# cyberlamp.net
KiCad netlist of a schematic drawn in Altium Designer
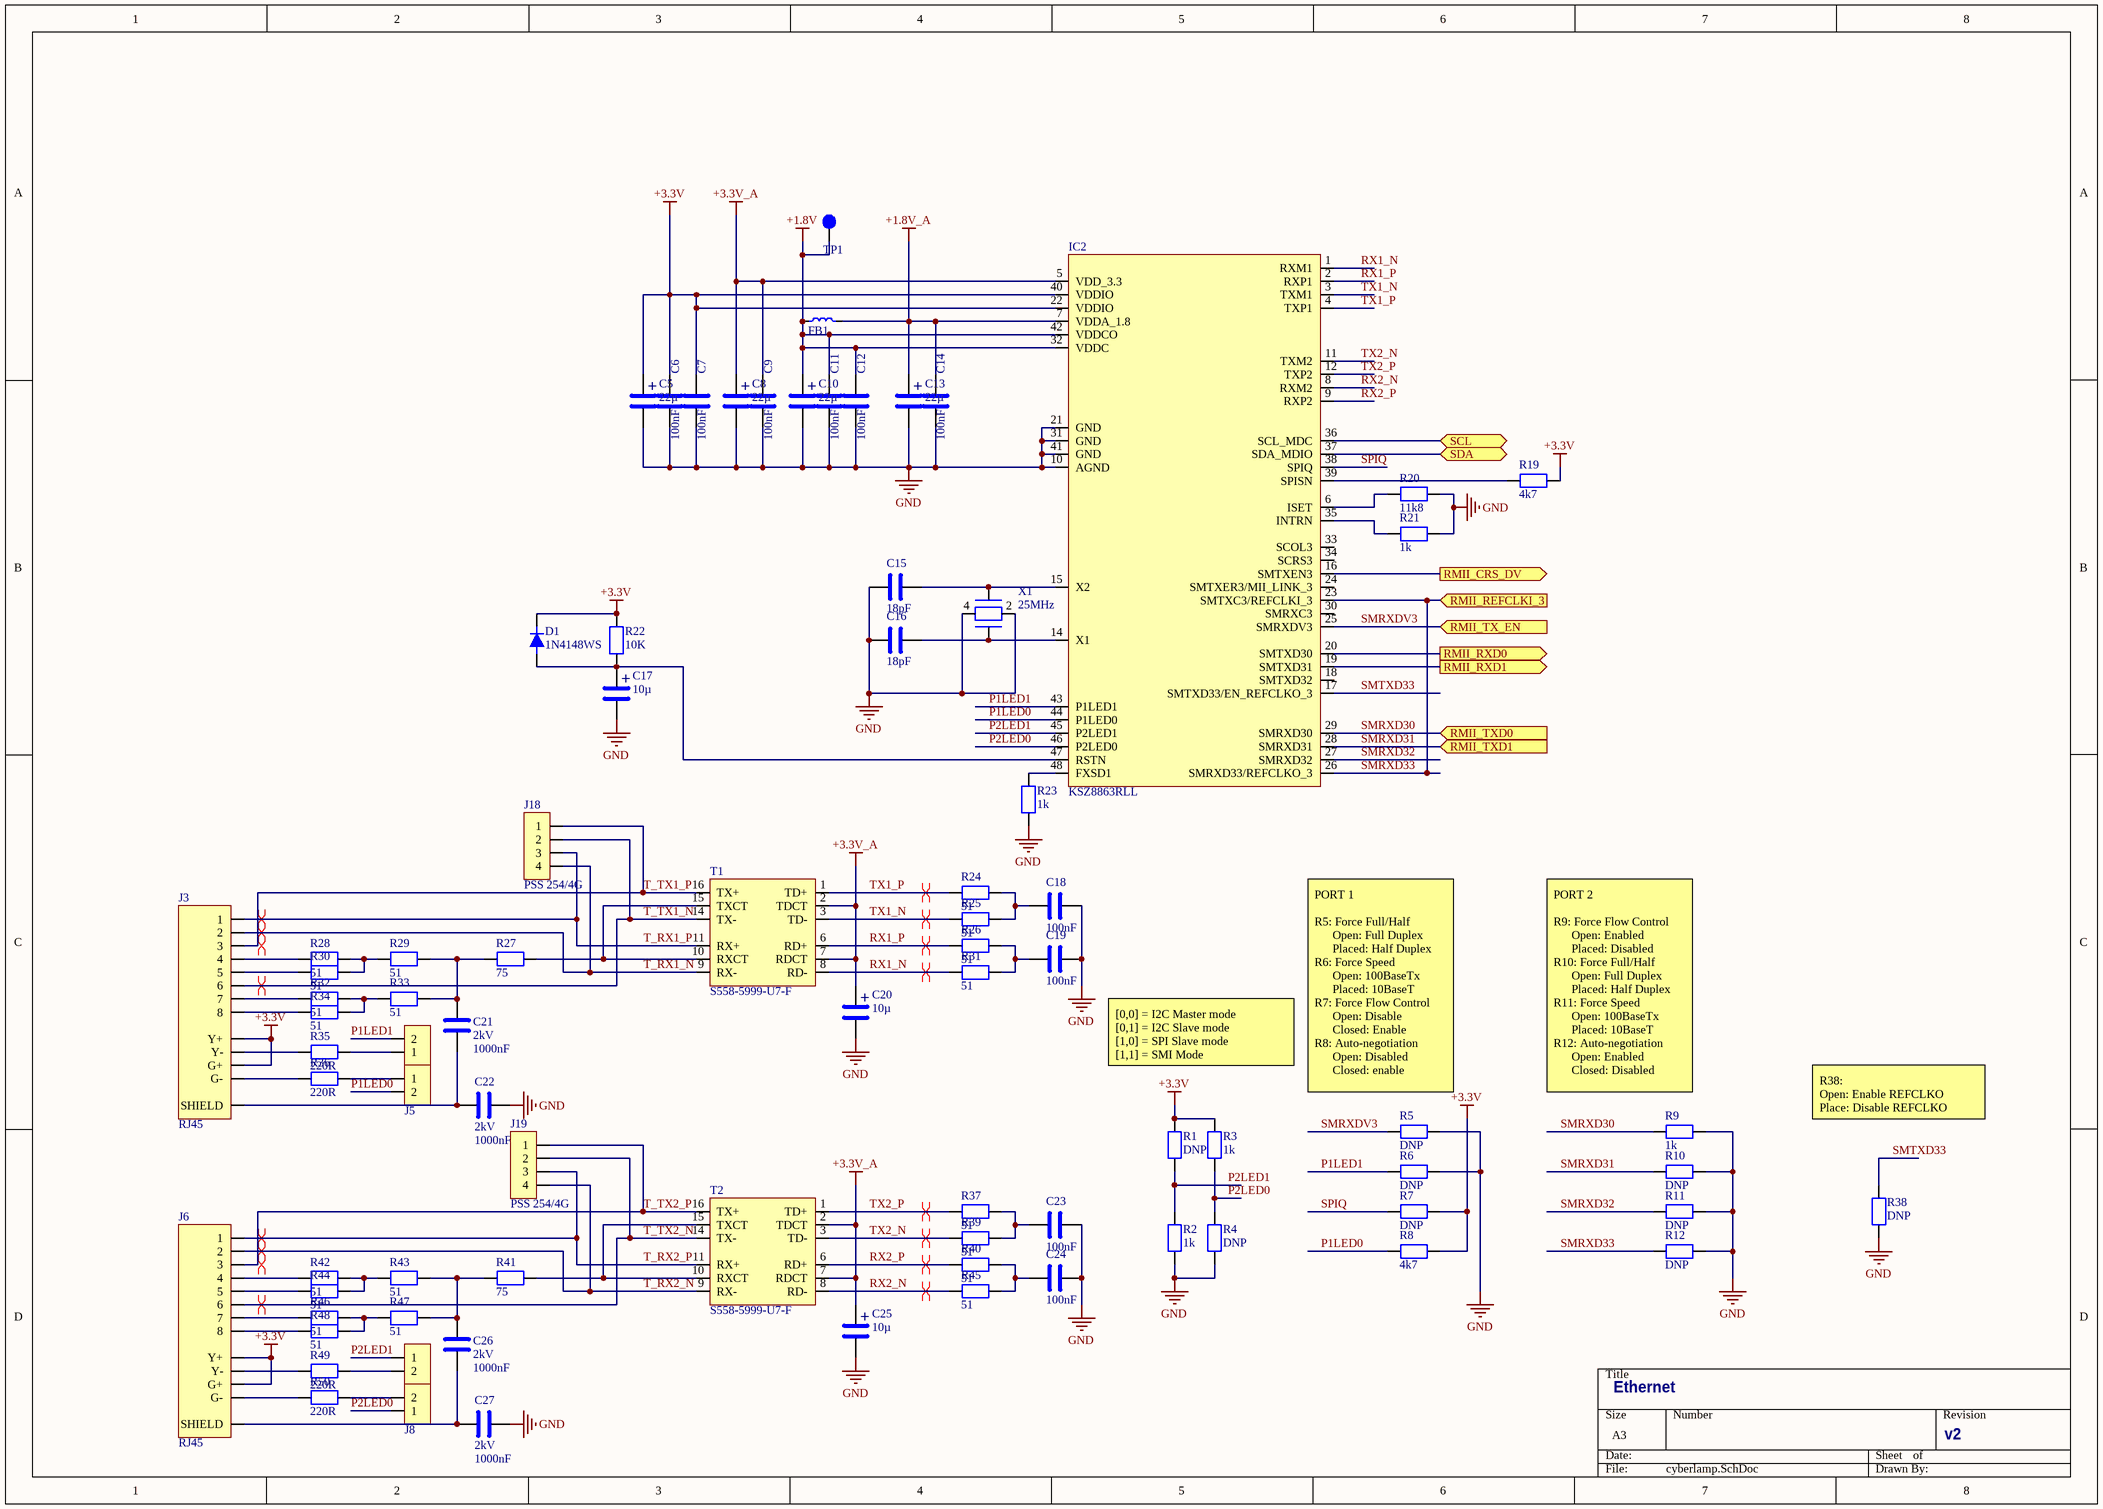
[diagram p0: cyberlamp.SchDoc]

(export (version "E")
  (design (tool "Eeschema 10.0.6"))
  (components
    (comp (ref "C5")
      (value "22µ")
      (footprint "WCAP-ASLU")
      (fields (field (name "VOLTAGE") "6.3V") (field (name "Comment") "Elko 22µF 6.3V WE"))
      (libsource (lib "elko") (part "Elko 22µF 6.3V WE"))
    )
    (comp (ref "C6")
      (value "100nF")
      (footprint "0603")
      (description "100nF 50V MLCC 0603")
      (fields (field (name "VOLTAGE") "50V"))
      (libsource (lib "capacitors") (part "100nF 50V MLCC 0603"))
    )
    (comp (ref "C7")
      (value "100nF")
      (footprint "0603")
      (description "100nF 50V MLCC 0603")
      (fields (field (name "VOLTAGE") "50V"))
      (libsource (lib "capacitors") (part "100nF 50V MLCC 0603"))
    )
    (comp (ref "C8")
      (value "22µ")
      (footprint "WCAP-ASLU")
      (fields (field (name "VOLTAGE") "6.3V") (field (name "Comment") "Elko 22µF 6.3V WE"))
      (libsource (lib "elko") (part "Elko 22µF 6.3V WE"))
    )
    (comp (ref "C9")
      (value "100nF")
      (footprint "0603")
      (description "100nF 50V MLCC 0603")
      (fields (field (name "VOLTAGE") "50V"))
      (libsource (lib "capacitors") (part "100nF 50V MLCC 0603"))
    )
    (comp (ref "C10")
      (value "22µ")
      (footprint "WCAP-ASLU")
      (fields (field (name "VOLTAGE") "6.3V") (field (name "Comment") "Elko 22µF 6.3V WE"))
      (libsource (lib "elko") (part "Elko 22µF 6.3V WE"))
    )
    (comp (ref "C11")
      (value "100nF")
      (footprint "0603")
      (description "100nF 50V MLCC 0603")
      (fields (field (name "VOLTAGE") "50V"))
      (libsource (lib "capacitors") (part "100nF 50V MLCC 0603"))
    )
    (comp (ref "C12")
      (value "100nF")
      (footprint "0603")
      (description "100nF 50V MLCC 0603")
      (fields (field (name "VOLTAGE") "50V"))
      (libsource (lib "capacitors") (part "100nF 50V MLCC 0603"))
    )
    (comp (ref "C13")
      (value "22µ")
      (footprint "WCAP-ASLU")
      (fields (field (name "VOLTAGE") "6.3V") (field (name "Comment") "Elko 22µF 6.3V WE"))
      (libsource (lib "elko") (part "Elko 22µF 6.3V WE"))
    )
    (comp (ref "C14")
      (value "100nF")
      (footprint "0603")
      (description "100nF 50V MLCC 0603")
      (fields (field (name "VOLTAGE") "50V"))
      (libsource (lib "capacitors") (part "100nF 50V MLCC 0603"))
    )
    (comp (ref "C15")
      (value "18pF")
      (footprint "0603")
      (description "18pF 50V MLCC 0603")
      (fields (field (name "VOLTAGE") "50V"))
      (libsource (lib "capacitors") (part "18pF 50V MLCC 0603"))
    )
    (comp (ref "C16")
      (value "18pF")
      (footprint "0603")
      (description "18pF 50V MLCC 0603")
      (fields (field (name "VOLTAGE") "50V"))
      (libsource (lib "capacitors") (part "18pF 50V MLCC 0603"))
    )
    (comp (ref "C17")
      (value "10µ")
      (footprint "Panasonic_b")
      (fields (field (name "VOLTAGE") "16V") (field (name "Comment") "Elko_10uF_16V_PanasonicB"))
      (libsource (lib "elkos") (part "Elko_10uF_16V_PanasonicB"))
    )
    (comp (ref "C18")
      (value "100nF")
      (footprint "0603")
      (description "100nF 50V MLCC 0603")
      (fields (field (name "VOLTAGE") "50V"))
      (libsource (lib "capacitors") (part "100nF 50V MLCC 0603"))
    )
    (comp (ref "C19")
      (value "100nF")
      (footprint "0603")
      (description "100nF 50V MLCC 0603")
      (fields (field (name "VOLTAGE") "50V"))
      (libsource (lib "capacitors") (part "100nF 50V MLCC 0603"))
    )
    (comp (ref "C20")
      (value "10µ")
      (footprint "Panasonic_b")
      (fields (field (name "VOLTAGE") "16V") (field (name "Comment") "Elko_10uF_16V_PanasonicB"))
      (libsource (lib "elkos") (part "Elko_10uF_16V_PanasonicB"))
    )
    (comp (ref "C21")
      (value "1000nF")
      (footprint "1206")
      (description "1000nF 2kV X7R 1206")
      (fields (field (name "VOLTAGE") "2kV") (field (name "Comment") "NP0"))
      (libsource (lib "capacitors") (part "1000nF 2kV X7R 1206"))
    )
    (comp (ref "C22")
      (value "1000nF")
      (footprint "1206")
      (description "1000nF 2kV X7R 1206")
      (fields (field (name "VOLTAGE") "2kV") (field (name "Comment") "NP0"))
      (libsource (lib "capacitors") (part "1000nF 2kV X7R 1206"))
    )
    (comp (ref "C23")
      (value "100nF")
      (footprint "0603")
      (description "100nF 50V MLCC 0603")
      (fields (field (name "VOLTAGE") "50V"))
      (libsource (lib "capacitors") (part "100nF 50V MLCC 0603"))
    )
    (comp (ref "C24")
      (value "100nF")
      (footprint "0603")
      (description "100nF 50V MLCC 0603")
      (fields (field (name "VOLTAGE") "50V"))
      (libsource (lib "capacitors") (part "100nF 50V MLCC 0603"))
    )
    (comp (ref "C25")
      (value "10µ")
      (footprint "Panasonic_b")
      (fields (field (name "VOLTAGE") "16V") (field (name "Comment") "Elko_10uF_16V_PanasonicB"))
      (libsource (lib "elkos") (part "Elko_10uF_16V_PanasonicB"))
    )
    (comp (ref "C26")
      (value "1000nF")
      (footprint "1206")
      (description "1000nF 2kV X7R 1206")
      (fields (field (name "VOLTAGE") "2kV") (field (name "Comment") "NP0"))
      (libsource (lib "capacitors") (part "1000nF 2kV X7R 1206"))
    )
    (comp (ref "C27")
      (value "1000nF")
      (footprint "1206")
      (description "1000nF 2kV X7R 1206")
      (fields (field (name "VOLTAGE") "2kV") (field (name "Comment") "NP0"))
      (libsource (lib "capacitors") (part "1000nF 2kV X7R 1206"))
    )
    (comp (ref "D1")
      (value "1N4148WS")
      (footprint "SOD323")
      (description "Small signal diode")
      (libsource (lib "diodes") (part "1N4148WS"))
    )
    (comp (ref "FB1")
      (value "HI1206N101R-10")
      (footprint "1206")
      (description "3A ferrit bead")
      (libsource (lib "inductors") (part "HI1206N101R-10"))
    )
    (comp (ref "IC2")
      (value "KSZ8863RLL")
      (footprint "LQFP48")
      (description "Dual port ethernet switch with RMII")
      (libsource (lib "misc") (part "KSZ8863RLL"))
    )
    (comp (ref "J3")
      (value "RJ45")
      (footprint "MTJ-88ARX1-FSM-PG-LH")
      (description "RJ45, shielded with LED")
      (libsource (lib "connectors_pc") (part "MTJ-88ARX1-FSM-PG-LH"))
    )
    (comp (ref "J4")
      (value "SL 1X2G 2,54")
      (footprint "SL_1x2 2.54mm")
      (description "Stiftleiste 2pol 2.54mm")
      (libsource (lib "connectors_sl") (part "SL 1X2G 2,54"))
    )
    (comp (ref "J5")
      (value "SL 1X2G 2,54")
      (footprint "SL_1x2 2.54mm")
      (description "Stiftleiste 2pol 2.54mm")
      (libsource (lib "") (part "SL 1X2G 2,54_1"))
    )
    (comp (ref "J6")
      (value "RJ45")
      (footprint "MTJ-88ARX1-FSM-PG-LH")
      (description "RJ45, shielded with LED")
      (libsource (lib "connectors_pc") (part "MTJ-88ARX1-FSM-PG-LH"))
    )
    (comp (ref "J7")
      (value "SL 1X2G 2,54")
      (footprint "SL_1x2 2.54mm")
      (description "Stiftleiste 2pol 2.54mm")
      (libsource (lib "") (part "SL 1X2G 2,54_1"))
    )
    (comp (ref "J8")
      (value "SL 1X2G 2,54")
      (footprint "SL_1x2 2.54mm")
      (description "Stiftleiste 2pol 2.54mm")
      (libsource (lib "connectors_sl") (part "SL 1X2G 2,54"))
    )
    (comp (ref "J18")
      (value "PSS 254/4G")
      (footprint "PSS 4pol")
      (description "PSS 4pol wire-to-board-connector")
      (libsource (lib "connectors_pss") (part "PSS 254/4G"))
    )
    (comp (ref "J19")
      (value "PSS 254/4G")
      (footprint "PSS 4pol")
      (description "PSS 4pol wire-to-board-connector")
      (libsource (lib "connectors_pss") (part "PSS 254/4G"))
    )
    (comp (ref "R1")
      (value "DNP")
      (footprint "res0603")
      (description "1k 100mW 0603")
      (fields (field (name "TOLERANCE") "1%"))
      (libsource (lib "resistors0603") (part "1k 100mW 0603"))
    )
    (comp (ref "R2")
      (value "1k")
      (footprint "res0603")
      (description "1k 100mW 0603")
      (fields (field (name "TOLERANCE") "1%"))
      (libsource (lib "resistors0603") (part "1k 100mW 0603"))
    )
    (comp (ref "R3")
      (value "1k")
      (footprint "res0603")
      (description "1k 100mW 0603")
      (fields (field (name "TOLERANCE") "1%"))
      (libsource (lib "resistors0603") (part "1k 100mW 0603"))
    )
    (comp (ref "R4")
      (value "DNP")
      (footprint "res0603")
      (description "1k 100mW 0603")
      (fields (field (name "TOLERANCE") "1%"))
      (libsource (lib "resistors0603") (part "1k 100mW 0603"))
    )
    (comp (ref "R5")
      (value "DNP")
      (footprint "res0603")
      (description "1k 100mW 0603")
      (fields (field (name "TOLERANCE") "1%"))
      (libsource (lib "resistors0603") (part "1k 100mW 0603"))
    )
    (comp (ref "R6")
      (value "DNP")
      (footprint "res0603")
      (description "1k 100mW 0603")
      (fields (field (name "TOLERANCE") "1%"))
      (libsource (lib "resistors0603") (part "1k 100mW 0603"))
    )
    (comp (ref "R7")
      (value "DNP")
      (footprint "res0603")
      (description "4k7 100mW 0603")
      (libsource (lib "resistors") (part "4k7 100mW 0603"))
    )
    (comp (ref "R8")
      (value "4k7")
      (footprint "res0603")
      (description "4k7 100mW 0603")
      (libsource (lib "resistors") (part "4k7 100mW 0603"))
    )
    (comp (ref "R9")
      (value "1k")
      (footprint "res0603")
      (description "1k 100mW 0603")
      (fields (field (name "TOLERANCE") "1%"))
      (libsource (lib "resistors0603") (part "1k 100mW 0603"))
    )
    (comp (ref "R10")
      (value "DNP")
      (footprint "res0603")
      (description "1k 100mW 0603")
      (fields (field (name "TOLERANCE") "1%"))
      (libsource (lib "resistors0603") (part "1k 100mW 0603"))
    )
    (comp (ref "R11")
      (value "DNP")
      (footprint "res0603")
      (description "1k 100mW 0603")
      (fields (field (name "TOLERANCE") "1%"))
      (libsource (lib "resistors0603") (part "1k 100mW 0603"))
    )
    (comp (ref "R12")
      (value "DNP")
      (footprint "res0603")
      (description "1k 100mW 0603")
      (fields (field (name "TOLERANCE") "1%"))
      (libsource (lib "resistors0603") (part "1k 100mW 0603"))
    )
    (comp (ref "R19")
      (value "4k7")
      (footprint "res0603")
      (description "4k7 100mW 0603")
      (libsource (lib "resistors") (part "4k7 100mW 0603"))
    )
    (comp (ref "R20")
      (value "11k8")
      (footprint "res0603")
      (description "11k8 100mW 0603")
      (fields (field (name "TOLERANCE") "1%"))
      (libsource (lib "resistors0603") (part "11k8 100mW 0603"))
    )
    (comp (ref "R21")
      (value "1k")
      (footprint "res0603")
      (description "1k 100mW 0603")
      (fields (field (name "TOLERANCE") "1%"))
      (libsource (lib "resistors0603") (part "1k 100mW 0603"))
    )
    (comp (ref "R22")
      (value "10K")
      (footprint "res0603")
      (description "10K 100mW 0603")
      (fields (field (name "TOLERANCE") "1%"))
      (libsource (lib "resistors") (part "10K 100mW 0603"))
    )
    (comp (ref "R23")
      (value "1k")
      (footprint "res0603")
      (description "1k 100mW 0603")
      (fields (field (name "TOLERANCE") "1%"))
      (libsource (lib "resistors0603") (part "1k 100mW 0603"))
    )
    (comp (ref "R24")
      (value "51")
      (footprint "res0603")
      (description "51 100mW 0603")
      (fields (field (name "TOLERANCE") "5%") (field (name "Comment") "51R 100mW 0603"))
      (libsource (lib "resistors0603") (part "51R 100mW 0603"))
    )
    (comp (ref "R25")
      (value "51")
      (footprint "res0603")
      (description "51 100mW 0603")
      (fields (field (name "TOLERANCE") "5%") (field (name "Comment") "51R 100mW 0603"))
      (libsource (lib "resistors0603") (part "51R 100mW 0603"))
    )
    (comp (ref "R26")
      (value "51")
      (footprint "res0603")
      (description "51 100mW 0603")
      (fields (field (name "TOLERANCE") "5%") (field (name "Comment") "51R 100mW 0603"))
      (libsource (lib "resistors0603") (part "51R 100mW 0603"))
    )
    (comp (ref "R27")
      (value "75")
      (footprint "res0603")
      (description "75 100mW 0603")
      (fields (field (name "TOLERANCE") "1%") (field (name "Comment") "75R 100mW 0603"))
      (libsource (lib "resistors0603") (part "75R 100mW 0603"))
    )
    (comp (ref "R28")
      (value "51")
      (footprint "res0603")
      (description "51 100mW 0603")
      (fields (field (name "TOLERANCE") "5%") (field (name "Comment") "51R 100mW 0603"))
      (libsource (lib "resistors0603") (part "51R 100mW 0603"))
    )
    (comp (ref "R29")
      (value "51")
      (footprint "res0603")
      (description "51 100mW 0603")
      (fields (field (name "TOLERANCE") "5%") (field (name "Comment") "51R 100mW 0603"))
      (libsource (lib "resistors0603") (part "51R 100mW 0603"))
    )
    (comp (ref "R30")
      (value "51")
      (footprint "res0603")
      (description "51 100mW 0603")
      (fields (field (name "TOLERANCE") "5%") (field (name "Comment") "51R 100mW 0603"))
      (libsource (lib "resistors0603") (part "51R 100mW 0603"))
    )
    (comp (ref "R31")
      (value "51")
      (footprint "res0603")
      (description "51 100mW 0603")
      (fields (field (name "TOLERANCE") "5%") (field (name "Comment") "51R 100mW 0603"))
      (libsource (lib "resistors0603") (part "51R 100mW 0603"))
    )
    (comp (ref "R32")
      (value "51")
      (footprint "res0603")
      (description "51 100mW 0603")
      (fields (field (name "TOLERANCE") "5%") (field (name "Comment") "51R 100mW 0603"))
      (libsource (lib "resistors0603") (part "51R 100mW 0603"))
    )
    (comp (ref "R33")
      (value "51")
      (footprint "res0603")
      (description "51 100mW 0603")
      (fields (field (name "TOLERANCE") "5%") (field (name "Comment") "51R 100mW 0603"))
      (libsource (lib "resistors0603") (part "51R 100mW 0603"))
    )
    (comp (ref "R34")
      (value "51")
      (footprint "res0603")
      (description "51 100mW 0603")
      (fields (field (name "TOLERANCE") "5%") (field (name "Comment") "51R 100mW 0603"))
      (libsource (lib "resistors0603") (part "51R 100mW 0603"))
    )
    (comp (ref "R35")
      (value "220R")
      (footprint "res0603")
      (description "220R 100mW 0603")
      (fields (field (name "TOLERANCE") "1%"))
      (libsource (lib "resistors0603") (part "220R 100mW 0603"))
    )
    (comp (ref "R36")
      (value "220R")
      (footprint "res0603")
      (description "220R 100mW 0603")
      (fields (field (name "TOLERANCE") "1%"))
      (libsource (lib "resistors0603") (part "220R 100mW 0603"))
    )
    (comp (ref "R37")
      (value "51")
      (footprint "res0603")
      (description "51 100mW 0603")
      (fields (field (name "TOLERANCE") "5%") (field (name "Comment") "51R 100mW 0603"))
      (libsource (lib "resistors0603") (part "51R 100mW 0603"))
    )
    (comp (ref "R38")
      (value "DNP")
      (footprint "res0603")
      (description "1k 100mW 0603")
      (fields (field (name "TOLERANCE") "1%"))
      (libsource (lib "resistors0603") (part "1k 100mW 0603"))
    )
    (comp (ref "R39")
      (value "51")
      (footprint "res0603")
      (description "51 100mW 0603")
      (fields (field (name "TOLERANCE") "5%") (field (name "Comment") "51R 100mW 0603"))
      (libsource (lib "resistors0603") (part "51R 100mW 0603"))
    )
    (comp (ref "R40")
      (value "51")
      (footprint "res0603")
      (description "51 100mW 0603")
      (fields (field (name "TOLERANCE") "5%") (field (name "Comment") "51R 100mW 0603"))
      (libsource (lib "resistors0603") (part "51R 100mW 0603"))
    )
    (comp (ref "R41")
      (value "75")
      (footprint "res0603")
      (description "75 100mW 0603")
      (fields (field (name "TOLERANCE") "1%") (field (name "Comment") "75R 100mW 0603"))
      (libsource (lib "resistors0603") (part "75R 100mW 0603"))
    )
    (comp (ref "R42")
      (value "51")
      (footprint "res0603")
      (description "51 100mW 0603")
      (fields (field (name "TOLERANCE") "5%") (field (name "Comment") "51R 100mW 0603"))
      (libsource (lib "resistors0603") (part "51R 100mW 0603"))
    )
    (comp (ref "R43")
      (value "51")
      (footprint "res0603")
      (description "51 100mW 0603")
      (fields (field (name "TOLERANCE") "5%") (field (name "Comment") "51R 100mW 0603"))
      (libsource (lib "resistors0603") (part "51R 100mW 0603"))
    )
    (comp (ref "R44")
      (value "51")
      (footprint "res0603")
      (description "51 100mW 0603")
      (fields (field (name "TOLERANCE") "5%") (field (name "Comment") "51R 100mW 0603"))
      (libsource (lib "resistors0603") (part "51R 100mW 0603"))
    )
    (comp (ref "R45")
      (value "51")
      (footprint "res0603")
      (description "51 100mW 0603")
      (fields (field (name "TOLERANCE") "5%") (field (name "Comment") "51R 100mW 0603"))
      (libsource (lib "resistors0603") (part "51R 100mW 0603"))
    )
    (comp (ref "R46")
      (value "51")
      (footprint "res0603")
      (description "51 100mW 0603")
      (fields (field (name "TOLERANCE") "5%") (field (name "Comment") "51R 100mW 0603"))
      (libsource (lib "resistors0603") (part "51R 100mW 0603"))
    )
    (comp (ref "R47")
      (value "51")
      (footprint "res0603")
      (description "51 100mW 0603")
      (fields (field (name "TOLERANCE") "5%") (field (name "Comment") "51R 100mW 0603"))
      (libsource (lib "resistors0603") (part "51R 100mW 0603"))
    )
    (comp (ref "R48")
      (value "51")
      (footprint "res0603")
      (description "51 100mW 0603")
      (fields (field (name "TOLERANCE") "5%") (field (name "Comment") "51R 100mW 0603"))
      (libsource (lib "resistors0603") (part "51R 100mW 0603"))
    )
    (comp (ref "R49")
      (value "220R")
      (footprint "res0603")
      (description "220R 100mW 0603")
      (fields (field (name "TOLERANCE") "1%"))
      (libsource (lib "resistors0603") (part "220R 100mW 0603"))
    )
    (comp (ref "R50")
      (value "220R")
      (footprint "res0603")
      (description "220R 100mW 0603")
      (fields (field (name "TOLERANCE") "1%"))
      (libsource (lib "resistors0603") (part "220R 100mW 0603"))
    )
    (comp (ref "T1")
      (value "S558-5999-U7-F")
      (footprint "S558-5999-U7-F")
      (description "Ethernet transformer")
      (libsource (lib "inductors2") (part "S558-5999-U7-F"))
    )
    (comp (ref "T2")
      (value "S558-5999-U7-F")
      (footprint "S558-5999-U7-F")
      (description "Ethernet transformer")
      (libsource (lib "inductors2") (part "S558-5999-U7-F"))
    )
    (comp (ref "TP1") (value "testpoint") (footprint "testpoint") (libsource (lib "misc") (part "testpoint")))
    (comp (ref "X1")
      (value "25MHz")
      (footprint "ABM8")
      (description "ABM8 25MHz crystal")
      (libsource (lib "crystals") (part "ABM8-25.000MHZ-B2-T"))
    )
  )
  (nets
    (net (code "1") (name "+1.8V") (class "Default")
      (node (ref "C10") (pin "+") (pinfunction "+_+") (pintype "passive"))
      (node (ref "C11") (pin "1") (pinfunction "1_1") (pintype "passive"))
      (node (ref "C12") (pin "1") (pinfunction "1_1") (pintype "passive"))
      (node (ref "FB1") (pin "1") (pinfunction "1_1") (pintype "passive"))
      (node (ref "IC2") (pin "32") (pinfunction "VDDC_32") (pintype "passive"))
      (node (ref "IC2") (pin "42") (pinfunction "VDDCO_42") (pintype "passive"))
      (node (ref "TP1") (pin "1") (pinfunction "1_1") (pintype "passive"))
    )
    (net (code "2") (name "+1.8V_A") (class "Default")
      (node (ref "C13") (pin "+") (pinfunction "+_+") (pintype "passive"))
      (node (ref "C14") (pin "1") (pinfunction "1_1") (pintype "passive"))
      (node (ref "FB1") (pin "2") (pinfunction "2_2") (pintype "passive"))
      (node (ref "IC2") (pin "7") (pinfunction "VDDA_1.8_7") (pintype "passive"))
    )
    (net (code "3") (name "+3.3V") (class "Default")
      (node (ref "C5") (pin "+") (pinfunction "+_+") (pintype "passive"))
      (node (ref "C6") (pin "1") (pinfunction "1_1") (pintype "passive"))
      (node (ref "C7") (pin "1") (pinfunction "1_1") (pintype "passive"))
      (node (ref "D1") (pin "1") (pinfunction "1_1") (pintype "passive"))
      (node (ref "IC2") (pin "22") (pinfunction "VDDIO_22") (pintype "passive"))
      (node (ref "IC2") (pin "40") (pinfunction "VDDIO_40") (pintype "passive"))
      (node (ref "J3") (pin "10") (pinfunction "Y+_10") (pintype "passive"))
      (node (ref "J3") (pin "12") (pinfunction "G+_12") (pintype "passive"))
      (node (ref "J6") (pin "10") (pinfunction "Y+_10") (pintype "passive"))
      (node (ref "J6") (pin "12") (pinfunction "G+_12") (pintype "passive"))
      (node (ref "R1") (pin "2") (pinfunction "2_2") (pintype "passive"))
      (node (ref "R19") (pin "1") (pinfunction "1_1") (pintype "passive"))
      (node (ref "R22") (pin "2") (pinfunction "2_2") (pintype "passive"))
      (node (ref "R3") (pin "2") (pinfunction "2_2") (pintype "passive"))
      (node (ref "R7") (pin "1") (pinfunction "1_1") (pintype "passive"))
      (node (ref "R8") (pin "1") (pinfunction "1_1") (pintype "passive"))
    )
    (net (code "4") (name "+3.3V_A") (class "Default")
      (node (ref "C20") (pin "+") (pinfunction "+_+") (pintype "passive"))
      (node (ref "C25") (pin "+") (pinfunction "+_+") (pintype "passive"))
      (node (ref "C8") (pin "+") (pinfunction "+_+") (pintype "passive"))
      (node (ref "C9") (pin "1") (pinfunction "1_1") (pintype "passive"))
      (node (ref "IC2") (pin "5") (pinfunction "VDD_3.3_5") (pintype "passive"))
      (node (ref "T1") (pin "2") (pinfunction "TDCT_2") (pintype "passive"))
      (node (ref "T1") (pin "7") (pinfunction "RDCT_7") (pintype "passive"))
      (node (ref "T2") (pin "2") (pinfunction "TDCT_2") (pintype "passive"))
      (node (ref "T2") (pin "7") (pinfunction "RDCT_7") (pintype "passive"))
    )
    (net (code "5") (name "/P1LED0") (class "Default")
      (node (ref "IC2") (pin "44") (pinfunction "P1LED0_44") (pintype "passive"))
      (node (ref "J5") (pin "2") (pinfunction "2_2") (pintype "passive"))
      (node (ref "R8") (pin "2") (pinfunction "2_2") (pintype "passive"))
    )
    (net (code "6") (name "/P1LED1") (class "Default")
      (node (ref "IC2") (pin "43") (pinfunction "P1LED1_43") (pintype "passive"))
      (node (ref "J4") (pin "2") (pinfunction "2_2") (pintype "passive"))
      (node (ref "R6") (pin "2") (pinfunction "2_2") (pintype "passive"))
    )
    (net (code "7") (name "/P2LED0") (class "Default")
      (node (ref "IC2") (pin "46") (pinfunction "P2LED0_46") (pintype "passive"))
      (node (ref "J8") (pin "1") (pinfunction "1_1") (pintype "passive"))
      (node (ref "R3") (pin "1") (pinfunction "1_1") (pintype "passive"))
      (node (ref "R4") (pin "2") (pinfunction "2_2") (pintype "passive"))
    )
    (net (code "8") (name "/P2LED1") (class "Default")
      (node (ref "IC2") (pin "45") (pinfunction "P2LED1_45") (pintype "passive"))
      (node (ref "J7") (pin "1") (pinfunction "1_1") (pintype "passive"))
      (node (ref "R1") (pin "1") (pinfunction "1_1") (pintype "passive"))
      (node (ref "R2") (pin "2") (pinfunction "2_2") (pintype "passive"))
    )
    (net (code "9") (name "/RMII_CRS_DV") (class "Default")
      (node (ref "IC2") (pin "16") (pinfunction "SMTXEN3_16") (pintype "passive"))
    )
    (net (code "10") (name "/RMII_RXD0") (class "Default")
      (node (ref "IC2") (pin "20") (pinfunction "SMTXD30_20") (pintype "passive"))
    )
    (net (code "11") (name "/RMII_RXD1") (class "Default")
      (node (ref "IC2") (pin "19") (pinfunction "SMTXD31_19") (pintype "passive"))
    )
    (net (code "12") (name "/RX1_N") (class "Default")
      (node (ref "IC2") (pin "1") (pinfunction "RXM1_1") (pintype "passive"))
      (node (ref "R31") (pin "2") (pinfunction "2_2") (pintype "passive"))
      (node (ref "T1") (pin "8") (pinfunction "RD-_8") (pintype "passive"))
    )
    (net (code "13") (name "/RX1_P") (class "Default")
      (node (ref "IC2") (pin "2") (pinfunction "RXP1_2") (pintype "passive"))
      (node (ref "R26") (pin "2") (pinfunction "2_2") (pintype "passive"))
      (node (ref "T1") (pin "6") (pinfunction "RD+_6") (pintype "passive"))
    )
    (net (code "14") (name "/RX2_N") (class "Default")
      (node (ref "IC2") (pin "8") (pinfunction "RXM2_8") (pintype "passive"))
      (node (ref "R45") (pin "2") (pinfunction "2_2") (pintype "passive"))
      (node (ref "T2") (pin "8") (pinfunction "RD-_8") (pintype "passive"))
    )
    (net (code "15") (name "/RX2_P") (class "Default")
      (node (ref "IC2") (pin "9") (pinfunction "RXP2_9") (pintype "passive"))
      (node (ref "R40") (pin "2") (pinfunction "2_2") (pintype "passive"))
      (node (ref "T2") (pin "6") (pinfunction "RD+_6") (pintype "passive"))
    )
    (net (code "16") (name "/SCL") (class "Default")
      (node (ref "IC2") (pin "36") (pinfunction "SCL_MDC_36") (pintype "passive"))
    )
    (net (code "17") (name "/SDA") (class "Default")
      (node (ref "IC2") (pin "37") (pinfunction "SDA_MDIO_37") (pintype "passive"))
    )
    (net (code "18") (name "/SMRXD30") (class "Default")
      (node (ref "IC2") (pin "29") (pinfunction "SMRXD30_29") (pintype "passive"))
      (node (ref "R9") (pin "2") (pinfunction "2_2") (pintype "passive"))
    )
    (net (code "19") (name "/SMRXD31") (class "Default")
      (node (ref "IC2") (pin "28") (pinfunction "SMRXD31_28") (pintype "passive"))
      (node (ref "R10") (pin "2") (pinfunction "2_2") (pintype "passive"))
    )
    (net (code "20") (name "/SMRXD32") (class "Default")
      (node (ref "IC2") (pin "27") (pinfunction "SMRXD32_27") (pintype "passive"))
      (node (ref "R11") (pin "2") (pinfunction "2_2") (pintype "passive"))
    )
    (net (code "21") (name "/SMRXD33") (class "Default")
      (node (ref "IC2") (pin "23") (pinfunction "SMTXC3/REFCLKI_3_23") (pintype "passive"))
      (node (ref "IC2") (pin "26") (pinfunction "SMRXD33/REFCLKO_3_26") (pintype "passive"))
      (node (ref "R12") (pin "2") (pinfunction "2_2") (pintype "passive"))
    )
    (net (code "22") (name "/SMRXDV3") (class "Default")
      (node (ref "IC2") (pin "25") (pinfunction "SMRXDV3_25") (pintype "passive"))
      (node (ref "R5") (pin "2") (pinfunction "2_2") (pintype "passive"))
    )
    (net (code "23") (name "/SMTXD33") (class "Default")
      (node (ref "IC2") (pin "17") (pinfunction "SMTXD33/EN_REFCLKO_3_17") (pintype "passive"))
      (node (ref "R38") (pin "1") (pinfunction "1_1") (pintype "passive"))
    )
    (net (code "24") (name "/SPIQ") (class "Default")
      (node (ref "IC2") (pin "38") (pinfunction "SPIQ_38") (pintype "passive"))
      (node (ref "R7") (pin "2") (pinfunction "2_2") (pintype "passive"))
    )
    (net (code "25") (name "/TX1_N") (class "Default")
      (node (ref "IC2") (pin "3") (pinfunction "TXM1_3") (pintype "passive"))
      (node (ref "R25") (pin "2") (pinfunction "2_2") (pintype "passive"))
      (node (ref "T1") (pin "3") (pinfunction "TD-_3") (pintype "passive"))
    )
    (net (code "26") (name "/TX1_P") (class "Default")
      (node (ref "IC2") (pin "4") (pinfunction "TXP1_4") (pintype "passive"))
      (node (ref "R24") (pin "2") (pinfunction "2_2") (pintype "passive"))
      (node (ref "T1") (pin "1") (pinfunction "TD+_1") (pintype "passive"))
    )
    (net (code "27") (name "/TX2_N") (class "Default")
      (node (ref "IC2") (pin "11") (pinfunction "TXM2_11") (pintype "passive"))
      (node (ref "R39") (pin "2") (pinfunction "2_2") (pintype "passive"))
      (node (ref "T2") (pin "3") (pinfunction "TD-_3") (pintype "passive"))
    )
    (net (code "28") (name "/TX2_P") (class "Default")
      (node (ref "IC2") (pin "12") (pinfunction "TXP2_12") (pintype "passive"))
      (node (ref "R37") (pin "2") (pinfunction "2_2") (pintype "passive"))
      (node (ref "T2") (pin "1") (pinfunction "TD+_1") (pintype "passive"))
    )
    (net (code "29") (name "/T_RX1_N") (class "Default")
      (node (ref "J18") (pin "4") (pinfunction "4_4") (pintype "passive"))
      (node (ref "J3") (pin "2") (pinfunction "2_2") (pintype "passive"))
      (node (ref "T1") (pin "9") (pinfunction "RX-_9") (pintype "passive"))
    )
    (net (code "30") (name "/T_RX1_P") (class "Default")
      (node (ref "J18") (pin "3") (pinfunction "3_3") (pintype "passive"))
      (node (ref "J3") (pin "1") (pinfunction "1_1") (pintype "passive"))
      (node (ref "T1") (pin "11") (pinfunction "RX+_11") (pintype "passive"))
    )
    (net (code "31") (name "/T_RX2_N") (class "Default")
      (node (ref "J19") (pin "4") (pinfunction "4_4") (pintype "passive"))
      (node (ref "J6") (pin "2") (pinfunction "2_2") (pintype "passive"))
      (node (ref "T2") (pin "9") (pinfunction "RX-_9") (pintype "passive"))
    )
    (net (code "32") (name "/T_RX2_P") (class "Default")
      (node (ref "J19") (pin "3") (pinfunction "3_3") (pintype "passive"))
      (node (ref "J6") (pin "1") (pinfunction "1_1") (pintype "passive"))
      (node (ref "T2") (pin "11") (pinfunction "RX+_11") (pintype "passive"))
    )
    (net (code "33") (name "/T_TX1_N") (class "Default")
      (node (ref "J18") (pin "2") (pinfunction "2_2") (pintype "passive"))
      (node (ref "J3") (pin "6") (pinfunction "6_6") (pintype "passive"))
      (node (ref "T1") (pin "14") (pinfunction "TX-_14") (pintype "passive"))
    )
    (net (code "34") (name "/T_TX1_P") (class "Default")
      (node (ref "J18") (pin "1") (pinfunction "1_1") (pintype "passive"))
      (node (ref "J3") (pin "3") (pinfunction "3_3") (pintype "passive"))
      (node (ref "T1") (pin "16") (pinfunction "TX+_16") (pintype "passive"))
    )
    (net (code "35") (name "/T_TX2_N") (class "Default")
      (node (ref "J19") (pin "2") (pinfunction "2_2") (pintype "passive"))
      (node (ref "J6") (pin "6") (pinfunction "6_6") (pintype "passive"))
      (node (ref "T2") (pin "14") (pinfunction "TX-_14") (pintype "passive"))
    )
    (net (code "36") (name "/T_TX2_P") (class "Default")
      (node (ref "J19") (pin "1") (pinfunction "1_1") (pintype "passive"))
      (node (ref "J6") (pin "3") (pinfunction "3_3") (pintype "passive"))
      (node (ref "T2") (pin "16") (pinfunction "TX+_16") (pintype "passive"))
    )
    (net (code "37") (name "GND") (class "Default")
      (node (ref "C10") (pin "-") (pinfunction "-_-") (pintype "passive"))
      (node (ref "C11") (pin "2") (pinfunction "2_2") (pintype "passive"))
      (node (ref "C12") (pin "2") (pinfunction "2_2") (pintype "passive"))
      (node (ref "C13") (pin "-") (pinfunction "-_-") (pintype "passive"))
      (node (ref "C14") (pin "2") (pinfunction "2_2") (pintype "passive"))
      (node (ref "C15") (pin "1") (pinfunction "1_1") (pintype "passive"))
      (node (ref "C16") (pin "1") (pinfunction "1_1") (pintype "passive"))
      (node (ref "C17") (pin "-") (pinfunction "-_-") (pintype "passive"))
      (node (ref "C18") (pin "2") (pinfunction "2_2") (pintype "passive"))
      (node (ref "C19") (pin "2") (pinfunction "2_2") (pintype "passive"))
      (node (ref "C20") (pin "-") (pinfunction "-_-") (pintype "passive"))
      (node (ref "C22") (pin "1") (pinfunction "1_1") (pintype "passive"))
      (node (ref "C23") (pin "2") (pinfunction "2_2") (pintype "passive"))
      (node (ref "C24") (pin "2") (pinfunction "2_2") (pintype "passive"))
      (node (ref "C25") (pin "-") (pinfunction "-_-") (pintype "passive"))
      (node (ref "C27") (pin "1") (pinfunction "1_1") (pintype "passive"))
      (node (ref "C5") (pin "-") (pinfunction "-_-") (pintype "passive"))
      (node (ref "C6") (pin "2") (pinfunction "2_2") (pintype "passive"))
      (node (ref "C7") (pin "2") (pinfunction "2_2") (pintype "passive"))
      (node (ref "C8") (pin "-") (pinfunction "-_-") (pintype "passive"))
      (node (ref "C9") (pin "2") (pinfunction "2_2") (pintype "passive"))
      (node (ref "IC2") (pin "10") (pinfunction "AGND_10") (pintype "passive"))
      (node (ref "IC2") (pin "21") (pinfunction "GND_21") (pintype "passive"))
      (node (ref "IC2") (pin "31") (pinfunction "GND_31") (pintype "passive"))
      (node (ref "IC2") (pin "41") (pinfunction "GND_41") (pintype "passive"))
      (node (ref "R10") (pin "1") (pinfunction "1_1") (pintype "passive"))
      (node (ref "R11") (pin "1") (pinfunction "1_1") (pintype "passive"))
      (node (ref "R12") (pin "1") (pinfunction "1_1") (pintype "passive"))
      (node (ref "R2") (pin "1") (pinfunction "1_1") (pintype "passive"))
      (node (ref "R20") (pin "1") (pinfunction "1_1") (pintype "passive"))
      (node (ref "R21") (pin "1") (pinfunction "1_1") (pintype "passive"))
      (node (ref "R23") (pin "2") (pinfunction "2_2") (pintype "passive"))
      (node (ref "R38") (pin "2") (pinfunction "2_2") (pintype "passive"))
      (node (ref "R4") (pin "1") (pinfunction "1_1") (pintype "passive"))
      (node (ref "R5") (pin "1") (pinfunction "1_1") (pintype "passive"))
      (node (ref "R6") (pin "1") (pinfunction "1_1") (pintype "passive"))
      (node (ref "R9") (pin "1") (pinfunction "1_1") (pintype "passive"))
      (node (ref "X1") (pin "2") (pinfunction "2_2") (pintype "passive"))
      (node (ref "X1") (pin "4") (pinfunction "4_4") (pintype "passive"))
    )
    (net (code "38") (name "Net-(C18-Pad1)") (class "Default")
      (node (ref "C18") (pin "1") (pinfunction "1_1") (pintype "passive"))
      (node (ref "R24") (pin "1") (pinfunction "1_1") (pintype "passive"))
      (node (ref "R25") (pin "1") (pinfunction "1_1") (pintype "passive"))
    )
    (net (code "39") (name "Net-(C19-Pad1)") (class "Default")
      (node (ref "C19") (pin "1") (pinfunction "1_1") (pintype "passive"))
      (node (ref "R26") (pin "1") (pinfunction "1_1") (pintype "passive"))
      (node (ref "R31") (pin "1") (pinfunction "1_1") (pintype "passive"))
    )
    (net (code "40") (name "Net-(C21-Pad2)") (class "Default")
      (node (ref "C21") (pin "2") (pinfunction "2_2") (pintype "passive"))
      (node (ref "R27") (pin "2") (pinfunction "2_2") (pintype "passive"))
      (node (ref "R29") (pin "1") (pinfunction "1_1") (pintype "passive"))
      (node (ref "R33") (pin "1") (pinfunction "1_1") (pintype "passive"))
    )
    (net (code "41") (name "Net-(C23-Pad1)") (class "Default")
      (node (ref "C23") (pin "1") (pinfunction "1_1") (pintype "passive"))
      (node (ref "R37") (pin "1") (pinfunction "1_1") (pintype "passive"))
      (node (ref "R39") (pin "1") (pinfunction "1_1") (pintype "passive"))
    )
    (net (code "42") (name "Net-(C24-Pad1)") (class "Default")
      (node (ref "C24") (pin "1") (pinfunction "1_1") (pintype "passive"))
      (node (ref "R40") (pin "1") (pinfunction "1_1") (pintype "passive"))
      (node (ref "R45") (pin "1") (pinfunction "1_1") (pintype "passive"))
    )
    (net (code "43") (name "Net-(C26-Pad2)") (class "Default")
      (node (ref "C26") (pin "2") (pinfunction "2_2") (pintype "passive"))
      (node (ref "R41") (pin "2") (pinfunction "2_2") (pintype "passive"))
      (node (ref "R43") (pin "1") (pinfunction "1_1") (pintype "passive"))
      (node (ref "R47") (pin "1") (pinfunction "1_1") (pintype "passive"))
    )
    (net (code "44") (name "Net-(IC2-FXSD1)") (class "Default")
      (node (ref "IC2") (pin "48") (pinfunction "FXSD1_48") (pintype "passive"))
      (node (ref "R23") (pin "1") (pinfunction "1_1") (pintype "passive"))
    )
    (net (code "45") (name "Net-(IC2-INTRN)") (class "Default")
      (node (ref "IC2") (pin "35") (pinfunction "INTRN_35") (pintype "passive"))
      (node (ref "R21") (pin "2") (pinfunction "2_2") (pintype "passive"))
    )
    (net (code "46") (name "Net-(IC2-ISET)") (class "Default")
      (node (ref "IC2") (pin "6") (pinfunction "ISET_6") (pintype "passive"))
      (node (ref "R20") (pin "2") (pinfunction "2_2") (pintype "passive"))
    )
    (net (code "47") (name "Net-(IC2-RSTN)") (class "Default")
      (node (ref "C17") (pin "+") (pinfunction "+_+") (pintype "passive"))
      (node (ref "D1") (pin "2") (pinfunction "2_2") (pintype "passive"))
      (node (ref "IC2") (pin "47") (pinfunction "RSTN_47") (pintype "passive"))
      (node (ref "R22") (pin "1") (pinfunction "1_1") (pintype "passive"))
    )
    (net (code "48") (name "Net-(IC2-SPISN)") (class "Default")
      (node (ref "IC2") (pin "39") (pinfunction "SPISN_39") (pintype "passive"))
      (node (ref "R19") (pin "2") (pinfunction "2_2") (pintype "passive"))
    )
    (net (code "49") (name "Net-(IC2-X1)") (class "Default")
      (node (ref "C16") (pin "2") (pinfunction "2_2") (pintype "passive"))
      (node (ref "IC2") (pin "14") (pinfunction "X1_14") (pintype "passive"))
      (node (ref "X1") (pin "3") (pinfunction "3_3") (pintype "passive"))
    )
    (net (code "50") (name "Net-(IC2-X2)") (class "Default")
      (node (ref "C15") (pin "2") (pinfunction "2_2") (pintype "passive"))
      (node (ref "IC2") (pin "15") (pinfunction "X2_15") (pintype "passive"))
      (node (ref "X1") (pin "1") (pinfunction "1_1") (pintype "passive"))
    )
    (net (code "51") (name "Net-(J3-G-)") (class "Default")
      (node (ref "J3") (pin "11") (pinfunction "G-_11") (pintype "passive"))
      (node (ref "R36") (pin "2") (pinfunction "2_2") (pintype "passive"))
    )
    (net (code "52") (name "Net-(J3-Pad4)") (class "Default")
      (node (ref "J3") (pin "4") (pinfunction "4_4") (pintype "passive"))
      (node (ref "R28") (pin "2") (pinfunction "2_2") (pintype "passive"))
    )
    (net (code "53") (name "Net-(J3-Pad5)") (class "Default")
      (node (ref "J3") (pin "5") (pinfunction "5_5") (pintype "passive"))
      (node (ref "R30") (pin "2") (pinfunction "2_2") (pintype "passive"))
    )
    (net (code "54") (name "Net-(J3-Pad7)") (class "Default")
      (node (ref "J3") (pin "7") (pinfunction "7_7") (pintype "passive"))
      (node (ref "R32") (pin "2") (pinfunction "2_2") (pintype "passive"))
    )
    (net (code "55") (name "Net-(J3-Pad8)") (class "Default")
      (node (ref "J3") (pin "8") (pinfunction "8_8") (pintype "passive"))
      (node (ref "R34") (pin "2") (pinfunction "2_2") (pintype "passive"))
    )
    (net (code "56") (name "Net-(J3-SHIELD)") (class "Default")
      (node (ref "C21") (pin "1") (pinfunction "1_1") (pintype "passive"))
      (node (ref "C22") (pin "2") (pinfunction "2_2") (pintype "passive"))
      (node (ref "J3") (pin "13") (pinfunction "SHIELD_13") (pintype "passive"))
    )
    (net (code "57") (name "Net-(J3-Y-)") (class "Default")
      (node (ref "J3") (pin "9") (pinfunction "Y-_9") (pintype "passive"))
      (node (ref "R35") (pin "2") (pinfunction "2_2") (pintype "passive"))
    )
    (net (code "58") (name "Net-(J4-Pad1)") (class "Default")
      (node (ref "J4") (pin "1") (pinfunction "1_1") (pintype "passive"))
      (node (ref "R35") (pin "1") (pinfunction "1_1") (pintype "passive"))
    )
    (net (code "59") (name "Net-(J5-Pad1)") (class "Default")
      (node (ref "J5") (pin "1") (pinfunction "1_1") (pintype "passive"))
      (node (ref "R36") (pin "1") (pinfunction "1_1") (pintype "passive"))
    )
    (net (code "60") (name "Net-(J6-G-)") (class "Default")
      (node (ref "J6") (pin "11") (pinfunction "G-_11") (pintype "passive"))
      (node (ref "R50") (pin "2") (pinfunction "2_2") (pintype "passive"))
    )
    (net (code "61") (name "Net-(J6-Pad4)") (class "Default")
      (node (ref "J6") (pin "4") (pinfunction "4_4") (pintype "passive"))
      (node (ref "R42") (pin "2") (pinfunction "2_2") (pintype "passive"))
    )
    (net (code "62") (name "Net-(J6-Pad5)") (class "Default")
      (node (ref "J6") (pin "5") (pinfunction "5_5") (pintype "passive"))
      (node (ref "R44") (pin "2") (pinfunction "2_2") (pintype "passive"))
    )
    (net (code "63") (name "Net-(J6-Pad7)") (class "Default")
      (node (ref "J6") (pin "7") (pinfunction "7_7") (pintype "passive"))
      (node (ref "R46") (pin "2") (pinfunction "2_2") (pintype "passive"))
    )
    (net (code "64") (name "Net-(J6-Pad8)") (class "Default")
      (node (ref "J6") (pin "8") (pinfunction "8_8") (pintype "passive"))
      (node (ref "R48") (pin "2") (pinfunction "2_2") (pintype "passive"))
    )
    (net (code "65") (name "Net-(J6-SHIELD)") (class "Default")
      (node (ref "C26") (pin "1") (pinfunction "1_1") (pintype "passive"))
      (node (ref "C27") (pin "2") (pinfunction "2_2") (pintype "passive"))
      (node (ref "J6") (pin "13") (pinfunction "SHIELD_13") (pintype "passive"))
    )
    (net (code "66") (name "Net-(J6-Y-)") (class "Default")
      (node (ref "J6") (pin "9") (pinfunction "Y-_9") (pintype "passive"))
      (node (ref "R49") (pin "2") (pinfunction "2_2") (pintype "passive"))
    )
    (net (code "67") (name "Net-(J7-Pad2)") (class "Default")
      (node (ref "J7") (pin "2") (pinfunction "2_2") (pintype "passive"))
      (node (ref "R49") (pin "1") (pinfunction "1_1") (pintype "passive"))
    )
    (net (code "68") (name "Net-(J8-Pad2)") (class "Default")
      (node (ref "J8") (pin "2") (pinfunction "2_2") (pintype "passive"))
      (node (ref "R50") (pin "1") (pinfunction "1_1") (pintype "passive"))
    )
    (net (code "69") (name "Net-(R28-Pad1)") (class "Default")
      (node (ref "R28") (pin "1") (pinfunction "1_1") (pintype "passive"))
      (node (ref "R29") (pin "2") (pinfunction "2_2") (pintype "passive"))
      (node (ref "R30") (pin "1") (pinfunction "1_1") (pintype "passive"))
    )
    (net (code "70") (name "Net-(R32-Pad1)") (class "Default")
      (node (ref "R32") (pin "1") (pinfunction "1_1") (pintype "passive"))
      (node (ref "R33") (pin "2") (pinfunction "2_2") (pintype "passive"))
      (node (ref "R34") (pin "1") (pinfunction "1_1") (pintype "passive"))
    )
    (net (code "71") (name "Net-(R42-Pad1)") (class "Default")
      (node (ref "R42") (pin "1") (pinfunction "1_1") (pintype "passive"))
      (node (ref "R43") (pin "2") (pinfunction "2_2") (pintype "passive"))
      (node (ref "R44") (pin "1") (pinfunction "1_1") (pintype "passive"))
    )
    (net (code "72") (name "Net-(R46-Pad1)") (class "Default")
      (node (ref "R46") (pin "1") (pinfunction "1_1") (pintype "passive"))
      (node (ref "R47") (pin "2") (pinfunction "2_2") (pintype "passive"))
      (node (ref "R48") (pin "1") (pinfunction "1_1") (pintype "passive"))
    )
    (net (code "73") (name "Net-(T1-RXCT)") (class "Default")
      (node (ref "R27") (pin "1") (pinfunction "1_1") (pintype "passive"))
      (node (ref "T1") (pin "10") (pinfunction "RXCT_10") (pintype "passive"))
      (node (ref "T1") (pin "15") (pinfunction "TXCT_15") (pintype "passive"))
    )
    (net (code "74") (name "Net-(T2-RXCT)") (class "Default")
      (node (ref "R41") (pin "1") (pinfunction "1_1") (pintype "passive"))
      (node (ref "T2") (pin "10") (pinfunction "RXCT_10") (pintype "passive"))
      (node (ref "T2") (pin "15") (pinfunction "TXCT_15") (pintype "passive"))
    )
    (net (code "75") (name "unconnected-(IC2-SCOL3-Pad33)") (class "Default")
      (node (ref "IC2") (pin "33") (pinfunction "SCOL3_33") (pintype "passive"))
    )
    (net (code "76") (name "unconnected-(IC2-SCRS3-Pad34)") (class "Default")
      (node (ref "IC2") (pin "34") (pinfunction "SCRS3_34") (pintype "passive"))
    )
    (net (code "77") (name "unconnected-(IC2-SMRXC3-Pad30)") (class "Default")
      (node (ref "IC2") (pin "30") (pinfunction "SMRXC3_30") (pintype "passive"))
    )
    (net (code "78") (name "unconnected-(IC2-SMTXD32-Pad18)") (class "Default")
      (node (ref "IC2") (pin "18") (pinfunction "SMTXD32_18") (pintype "passive"))
    )
    (net (code "79") (name "unconnected-(IC2-SMTXER3{slash}MII_LINK_3-Pad24)") (class "Default")
      (node (ref "IC2") (pin "24") (pinfunction "SMTXER3/MII_LINK_3_24") (pintype "passive"))
    )
  )
)
